# Fujin_Motors.net
KiCad netlist of a schematic drawn in Altium Designer
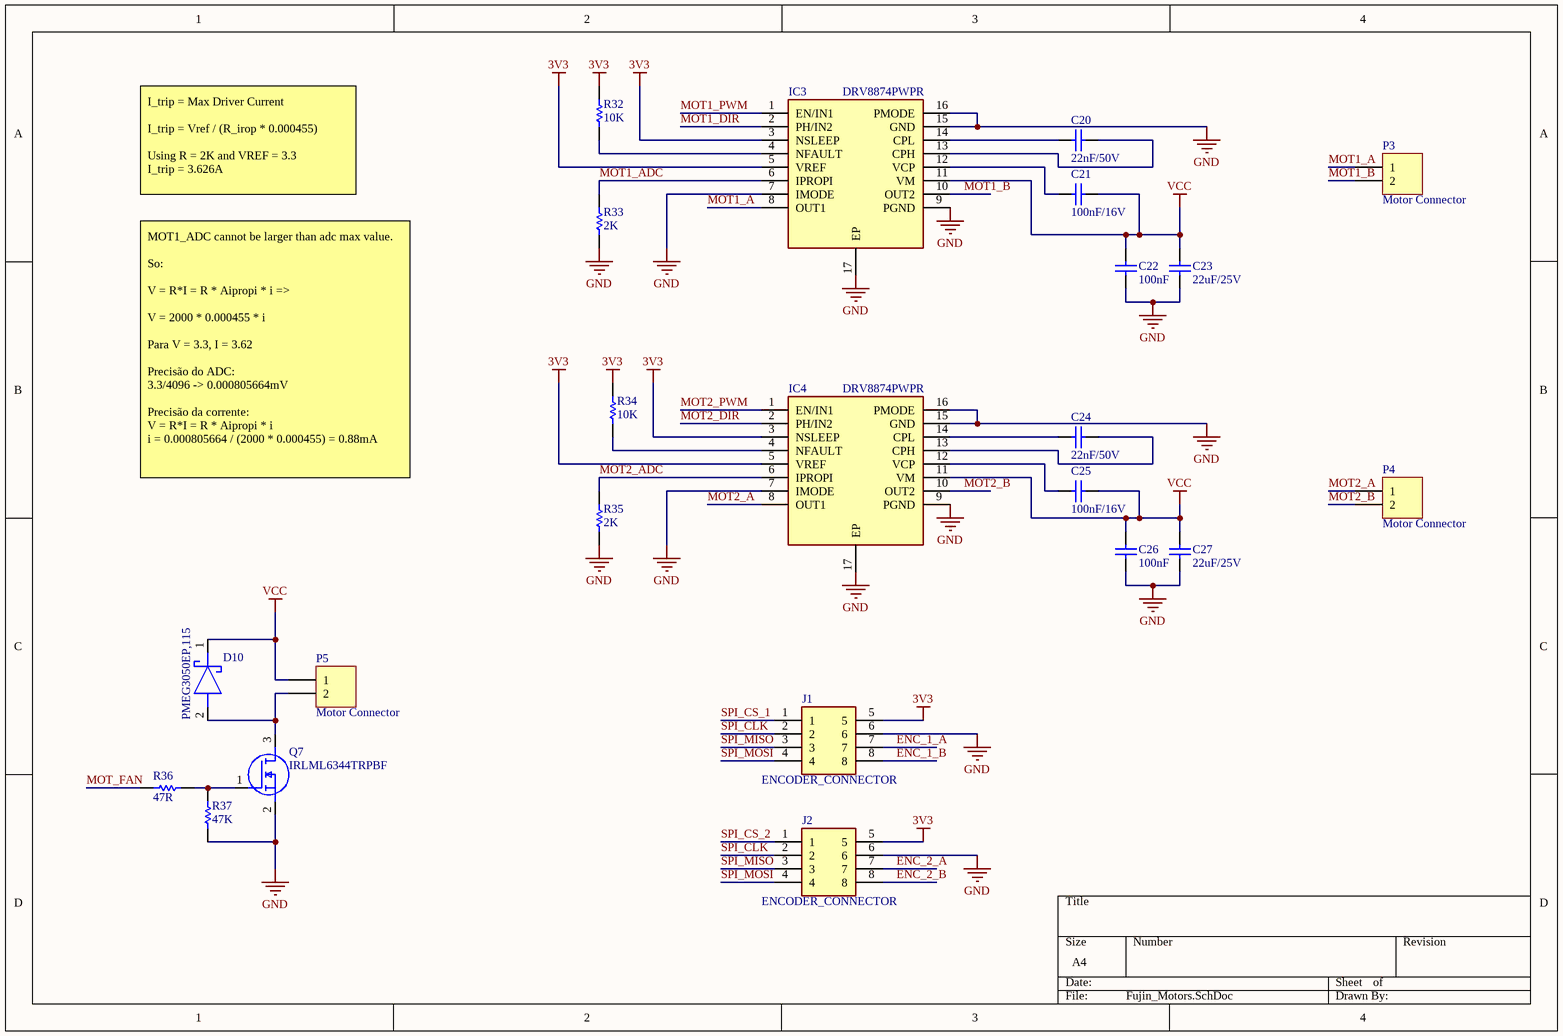
[diagram p0: Fujin_Motors.SchDoc]

(export (version "E")
  (design (tool "Eeschema 10.0.6"))
  (components
    (comp (ref "C20")
      (value "22nF/50V")
      (footprint "Capacitor-0603")
      (description "Capacitor Cer 22nF 50V")
      (fields (field (name "MANUFACTURER PART NUMBER") "IMP14925"))
      (libsource (lib "FujinLib") (part "CAP 22nF"))
    )
    (comp (ref "C21")
      (value "100nF/16V")
      (footprint "Capacitor-0603")
      (description "Capacitor Cer 100nF 16VX7R")
      (fields (field (name "MANUFACTURER PART NUMBER") "IMP14925"))
      (libsource (lib "FujinLib") (part "CAP 100NF 16V"))
    )
    (comp (ref "C22")
      (value "100nF")
      (footprint "Capacitor-0603")
      (description "Capacitor Cer 100nF 50V")
      (fields (field (name "MANUFACTURER PART NUMBER") "IMP14925"))
      (libsource (lib "FujinLib") (part "CAP 100NF 50V"))
    )
    (comp (ref "C23")
      (value "22uF/25V")
      (footprint "CAPACITOR-0805")
      (description "CAP CER 22UF 25V X5R 0805")
      (fields
        (field (name "MANUFACTURER") "AVX Corporation")
        (field (name "MANUFACTURER PART NUMBER") "0805YD106KAT2A")
      )
      (libsource (lib "FujinLib") (part "CAP CER 22UF 25V X5R 0805"))
    )
    (comp (ref "C24")
      (value "22nF/50V")
      (footprint "Capacitor-0603")
      (description "Capacitor Cer 22nF 50V")
      (fields (field (name "MANUFACTURER PART NUMBER") "IMP14925"))
      (libsource (lib "FujinLib") (part "CAP 22nF"))
    )
    (comp (ref "C25")
      (value "100nF/16V")
      (footprint "Capacitor-0603")
      (description "Capacitor Cer 100nF 16VX7R")
      (fields (field (name "MANUFACTURER PART NUMBER") "IMP14925"))
      (libsource (lib "FujinLib") (part "CAP 100NF 16V"))
    )
    (comp (ref "C26")
      (value "100nF")
      (footprint "Capacitor-0603")
      (description "Capacitor Cer 100nF 50V")
      (fields (field (name "MANUFACTURER PART NUMBER") "IMP14925"))
      (libsource (lib "FujinLib") (part "CAP 100NF 50V"))
    )
    (comp (ref "C27")
      (value "22uF/25V")
      (footprint "CAPACITOR-0805")
      (description "CAP CER 22UF 25V X5R 0805")
      (fields
        (field (name "MANUFACTURER") "AVX Corporation")
        (field (name "MANUFACTURER PART NUMBER") "0805YD106KAT2A")
      )
      (libsource (lib "FujinLib") (part "CAP CER 22UF 25V X5R 0805"))
    )
    (comp (ref "D10")
      (value "PMEG3050EP,115")
      (footprint "PMEG3050EP115")
      (description "Schottky Diode")
      (fields (field (name "MOUSER PART NUMBER") "771-PMEG3050EP115"))
      (libsource (lib "FujinLib") (part "PMEG3050EP,115"))
    )
    (comp (ref "IC3")
      (value "DRV8874PWPR")
      (footprint "SOP65P640X120-17N")
      (description "Integrated Circuit")
      (fields (field (name "MOUSER PART NUMBER") "595-DRV8874PWPR"))
      (libsource (lib "FujinLib") (part "DRV8874PWPR"))
    )
    (comp (ref "IC4")
      (value "DRV8874PWPR")
      (footprint "SOP65P640X120-17N")
      (description "Integrated Circuit")
      (fields (field (name "MOUSER PART NUMBER") "595-DRV8874PWPR"))
      (libsource (lib "FujinLib") (part "DRV8874PWPR"))
    )
    (comp (ref "J1")
      (value "ENCODER_CONNECTOR")
      (footprint "ENCODER_CONN")
      (libsource (lib "FujinLib") (part "ENCODER_CONNECTOR"))
    )
    (comp (ref "J2")
      (value "ENCODER_CONNECTOR")
      (footprint "ENCODER_CONN")
      (libsource (lib "FujinLib") (part "ENCODER_CONNECTOR"))
    )
    (comp (ref "P3")
      (value "Motor Connector")
      (footprint "MOTOR_CONNECTOR")
      (libsource (lib "FujinLib") (part "Motor Connector"))
    )
    (comp (ref "P4")
      (value "Motor Connector")
      (footprint "MOTOR_CONNECTOR")
      (libsource (lib "FujinLib") (part "Motor Connector"))
    )
    (comp (ref "P5")
      (value "Motor Connector")
      (footprint "MOTOR_CONNECTOR")
      (libsource (lib "FujinLib") (part "Motor Connector"))
    )
    (comp (ref "Q7")
      (value "IRLML6344TRPBF")
      (footprint "SOT95P237X112-3N")
      (description "MOSFET (N-Channel)")
      (fields (field (name "MOUSER PART NUMBER") "942-IRLML6344TRPBF"))
      (libsource (lib "FujinLib") (part "IRLML6344TRPBF"))
    )
    (comp (ref "R32")
      (value "10K")
      (footprint "RESISTOR 0402")
      (fields
        (field (name "MANUFACTURER") "PANASONIC ELECTRONIC COMPONENTS")
        (field (name "MANUFACTURER PART NUMBER") "ERJ-3GEYJ103V")
        (field (name "TOLERANCE") "±5%")
      )
      (libsource (lib "FujinLib") (part "RES 10K 5%"))
    )
    (comp (ref "R33")
      (value "2K")
      (footprint "RESISTOR 0603")
      (description "Resistor 2K 1% tolerance")
      (fields (field (name "MANUFACTURER") "Ty-Ohm") (field (name "MANUFACTURER PART NUMBER") "CR25"))
      (libsource (lib "FujinLib") (part "RES 2K 1%_1"))
    )
    (comp (ref "R34")
      (value "10K")
      (footprint "RESISTOR 0402")
      (fields
        (field (name "MANUFACTURER") "PANASONIC ELECTRONIC COMPONENTS")
        (field (name "MANUFACTURER PART NUMBER") "ERJ-3GEYJ103V")
        (field (name "TOLERANCE") "±5%")
      )
      (libsource (lib "FujinLib") (part "RES 10K 5%"))
    )
    (comp (ref "R35")
      (value "2K")
      (footprint "RESISTOR 0603")
      (description "Resistor 2K 1% tolerance")
      (fields (field (name "MANUFACTURER") "Ty-Ohm") (field (name "MANUFACTURER PART NUMBER") "CR25"))
      (libsource (lib "FujinLib") (part "RES 2K 1%_1"))
    )
    (comp (ref "R36")
      (value "47R")
      (footprint "RESISTOR 0402")
      (fields
        (field (name "MANUFACTURER") "Ty-Ohm")
        (field (name "MANUFACTURER PART NUMBER") "CR25")
        (field (name "TOLERANCE") "±5%")
      )
      (libsource (lib "FujinLib") (part "RES 47R 5%"))
    )
    (comp (ref "R37")
      (value "47K")
      (footprint "RESISTOR 0402")
      (fields
        (field (name "MANUFACTURER") "Ty-Ohm")
        (field (name "MANUFACTURER PART NUMBER") "CR25")
        (field (name "TOLERANCE") "±5%")
      )
      (libsource (lib "FujinLib") (part "RES 47K 5%"))
    )
  )
  (nets
    (net (code "1") (name "/ENC_1_A") (class "Default")
      (node (ref "J1") (pin "7") (pinfunction "7_7") (pintype "passive"))
    )
    (net (code "2") (name "/ENC_1_B") (class "Default")
      (node (ref "J1") (pin "8") (pinfunction "8_8") (pintype "passive"))
    )
    (net (code "3") (name "/ENC_2_A") (class "Default")
      (node (ref "J2") (pin "7") (pinfunction "7_7") (pintype "passive"))
    )
    (net (code "4") (name "/ENC_2_B") (class "Default")
      (node (ref "J2") (pin "8") (pinfunction "8_8") (pintype "passive"))
    )
    (net (code "5") (name "/MOT1_A") (class "Default")
      (node (ref "IC3") (pin "8") (pinfunction "OUT1_8") (pintype "passive"))
      (node (ref "P3") (pin "1") (pinfunction "1_1") (pintype "passive"))
    )
    (net (code "6") (name "/MOT1_ADC") (class "Default")
      (node (ref "IC3") (pin "6") (pinfunction "IPROPI_6") (pintype "passive"))
      (node (ref "R33") (pin "2") (pinfunction "2_2") (pintype "passive"))
    )
    (net (code "7") (name "/MOT1_B") (class "Default")
      (node (ref "IC3") (pin "10") (pinfunction "OUT2_10") (pintype "passive"))
      (node (ref "P3") (pin "2") (pinfunction "2_2") (pintype "passive"))
    )
    (net (code "8") (name "/MOT1_DIR") (class "Default")
      (node (ref "IC3") (pin "2") (pinfunction "PH/IN2_2") (pintype "passive"))
    )
    (net (code "9") (name "/MOT1_PWM") (class "Default")
      (node (ref "IC3") (pin "1") (pinfunction "EN/IN1_1") (pintype "passive"))
    )
    (net (code "10") (name "/MOT2_A") (class "Default")
      (node (ref "IC4") (pin "8") (pinfunction "OUT1_8") (pintype "passive"))
      (node (ref "P4") (pin "1") (pinfunction "1_1") (pintype "passive"))
    )
    (net (code "11") (name "/MOT2_ADC") (class "Default")
      (node (ref "IC4") (pin "6") (pinfunction "IPROPI_6") (pintype "passive"))
      (node (ref "R35") (pin "2") (pinfunction "2_2") (pintype "passive"))
    )
    (net (code "12") (name "/MOT2_B") (class "Default")
      (node (ref "IC4") (pin "10") (pinfunction "OUT2_10") (pintype "passive"))
      (node (ref "P4") (pin "2") (pinfunction "2_2") (pintype "passive"))
    )
    (net (code "13") (name "/MOT2_DIR") (class "Default")
      (node (ref "IC4") (pin "2") (pinfunction "PH/IN2_2") (pintype "passive"))
    )
    (net (code "14") (name "/MOT2_PWM") (class "Default")
      (node (ref "IC4") (pin "1") (pinfunction "EN/IN1_1") (pintype "passive"))
    )
    (net (code "15") (name "/MOT_FAN") (class "Default")
      (node (ref "R36") (pin "1") (pinfunction "1_1") (pintype "passive"))
    )
    (net (code "16") (name "/SPI_CLK") (class "Default")
      (node (ref "J1") (pin "2") (pinfunction "2_2") (pintype "passive"))
      (node (ref "J2") (pin "2") (pinfunction "2_2") (pintype "passive"))
    )
    (net (code "17") (name "/SPI_CS_1") (class "Default")
      (node (ref "J1") (pin "1") (pinfunction "1_1") (pintype "passive"))
    )
    (net (code "18") (name "/SPI_CS_2") (class "Default")
      (node (ref "J2") (pin "1") (pinfunction "1_1") (pintype "passive"))
    )
    (net (code "19") (name "/SPI_MISO") (class "Default")
      (node (ref "J1") (pin "3") (pinfunction "3_3") (pintype "passive"))
      (node (ref "J2") (pin "3") (pinfunction "3_3") (pintype "passive"))
    )
    (net (code "20") (name "/SPI_MOSI") (class "Default")
      (node (ref "J1") (pin "4") (pinfunction "4_4") (pintype "passive"))
      (node (ref "J2") (pin "4") (pinfunction "4_4") (pintype "passive"))
    )
    (net (code "21") (name "3V3") (class "Default")
      (node (ref "IC3") (pin "3") (pinfunction "NSLEEP_3") (pintype "passive"))
      (node (ref "IC3") (pin "5") (pinfunction "VREF_5") (pintype "passive"))
      (node (ref "IC4") (pin "3") (pinfunction "NSLEEP_3") (pintype "passive"))
      (node (ref "IC4") (pin "5") (pinfunction "VREF_5") (pintype "passive"))
      (node (ref "J1") (pin "5") (pinfunction "5_5") (pintype "passive"))
      (node (ref "J2") (pin "5") (pinfunction "5_5") (pintype "passive"))
      (node (ref "R32") (pin "2") (pinfunction "2_2") (pintype "passive"))
      (node (ref "R34") (pin "2") (pinfunction "2_2") (pintype "passive"))
    )
    (net (code "22") (name "GND") (class "Default")
      (node (ref "C22") (pin "1") (pinfunction "1_1") (pintype "passive"))
      (node (ref "C23") (pin "1") (pinfunction "1_1") (pintype "passive"))
      (node (ref "C26") (pin "1") (pinfunction "1_1") (pintype "passive"))
      (node (ref "C27") (pin "1") (pinfunction "1_1") (pintype "passive"))
      (node (ref "IC3") (pin "15") (pinfunction "GND_15") (pintype "passive"))
      (node (ref "IC3") (pin "16") (pinfunction "PMODE_16") (pintype "passive"))
      (node (ref "IC3") (pin "17") (pinfunction "EP_17") (pintype "passive"))
      (node (ref "IC3") (pin "7") (pinfunction "IMODE_7") (pintype "passive"))
      (node (ref "IC3") (pin "9") (pinfunction "PGND_9") (pintype "passive"))
      (node (ref "IC4") (pin "15") (pinfunction "GND_15") (pintype "passive"))
      (node (ref "IC4") (pin "16") (pinfunction "PMODE_16") (pintype "passive"))
      (node (ref "IC4") (pin "17") (pinfunction "EP_17") (pintype "passive"))
      (node (ref "IC4") (pin "7") (pinfunction "IMODE_7") (pintype "passive"))
      (node (ref "IC4") (pin "9") (pinfunction "PGND_9") (pintype "passive"))
      (node (ref "J1") (pin "6") (pinfunction "6_6") (pintype "passive"))
      (node (ref "J2") (pin "6") (pinfunction "6_6") (pintype "passive"))
      (node (ref "Q7") (pin "2") (pinfunction "S_2") (pintype "passive"))
      (node (ref "R33") (pin "1") (pinfunction "1_1") (pintype "passive"))
      (node (ref "R35") (pin "1") (pinfunction "1_1") (pintype "passive"))
      (node (ref "R37") (pin "1") (pinfunction "1_1") (pintype "passive"))
    )
    (net (code "23") (name "Net-(D10-A)") (class "Default")
      (node (ref "D10") (pin "2") (pinfunction "A_2") (pintype "passive"))
      (node (ref "P5") (pin "2") (pinfunction "2_2") (pintype "passive"))
      (node (ref "Q7") (pin "3") (pinfunction "D_3") (pintype "passive"))
    )
    (net (code "24") (name "Net-(IC3-CPH)") (class "Default")
      (node (ref "C20") (pin "2") (pinfunction "2_2") (pintype "passive"))
      (node (ref "IC3") (pin "13") (pinfunction "CPH_13") (pintype "passive"))
    )
    (net (code "25") (name "Net-(IC3-CPL)") (class "Default")
      (node (ref "C20") (pin "1") (pinfunction "1_1") (pintype "passive"))
      (node (ref "IC3") (pin "14") (pinfunction "CPL_14") (pintype "passive"))
    )
    (net (code "26") (name "Net-(IC3-NFAULT)") (class "Default")
      (node (ref "IC3") (pin "4") (pinfunction "NFAULT_4") (pintype "passive"))
      (node (ref "R32") (pin "1") (pinfunction "1_1") (pintype "passive"))
    )
    (net (code "27") (name "Net-(IC3-VCP)") (class "Default")
      (node (ref "C21") (pin "1") (pinfunction "1_1") (pintype "passive"))
      (node (ref "IC3") (pin "12") (pinfunction "VCP_12") (pintype "passive"))
    )
    (net (code "28") (name "Net-(IC4-CPH)") (class "Default")
      (node (ref "C24") (pin "2") (pinfunction "2_2") (pintype "passive"))
      (node (ref "IC4") (pin "13") (pinfunction "CPH_13") (pintype "passive"))
    )
    (net (code "29") (name "Net-(IC4-CPL)") (class "Default")
      (node (ref "C24") (pin "1") (pinfunction "1_1") (pintype "passive"))
      (node (ref "IC4") (pin "14") (pinfunction "CPL_14") (pintype "passive"))
    )
    (net (code "30") (name "Net-(IC4-NFAULT)") (class "Default")
      (node (ref "IC4") (pin "4") (pinfunction "NFAULT_4") (pintype "passive"))
      (node (ref "R34") (pin "1") (pinfunction "1_1") (pintype "passive"))
    )
    (net (code "31") (name "Net-(IC4-VCP)") (class "Default")
      (node (ref "C25") (pin "1") (pinfunction "1_1") (pintype "passive"))
      (node (ref "IC4") (pin "12") (pinfunction "VCP_12") (pintype "passive"))
    )
    (net (code "32") (name "Net-(Q7-G)") (class "Default")
      (node (ref "Q7") (pin "1") (pinfunction "G_1") (pintype "passive"))
      (node (ref "R36") (pin "2") (pinfunction "2_2") (pintype "passive"))
      (node (ref "R37") (pin "2") (pinfunction "2_2") (pintype "passive"))
    )
    (net (code "33") (name "VCC") (class "Default")
      (node (ref "C21") (pin "2") (pinfunction "2_2") (pintype "passive"))
      (node (ref "C22") (pin "2") (pinfunction "2_2") (pintype "passive"))
      (node (ref "C23") (pin "2") (pinfunction "2_2") (pintype "passive"))
      (node (ref "C25") (pin "2") (pinfunction "2_2") (pintype "passive"))
      (node (ref "C26") (pin "2") (pinfunction "2_2") (pintype "passive"))
      (node (ref "C27") (pin "2") (pinfunction "2_2") (pintype "passive"))
      (node (ref "D10") (pin "1") (pinfunction "K_1") (pintype "passive"))
      (node (ref "IC3") (pin "11") (pinfunction "VM_11") (pintype "passive"))
      (node (ref "IC4") (pin "11") (pinfunction "VM_11") (pintype "passive"))
      (node (ref "P5") (pin "1") (pinfunction "1_1") (pintype "passive"))
    )
  )
)
